# PrzyciskDotykowy_A4_Landscape.net
KiCad netlist of a schematic drawn in Altium Designer
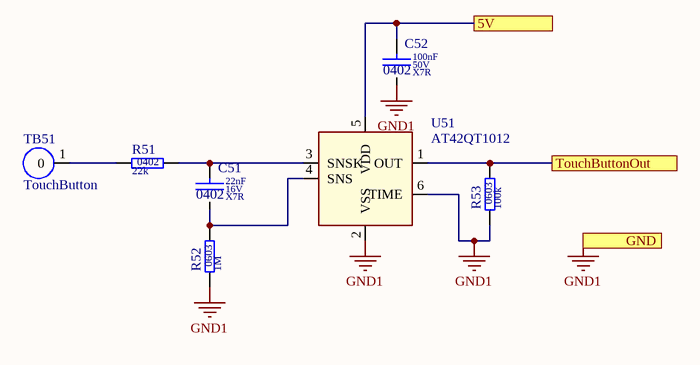
[diagram p0: PrzyciskDotykowy_A4_Landscape_.SchDoc]

(export (version "E")
  (design (tool "Eeschema 10.0.6"))
  (components
    (comp (ref "C51")
      (value "22nF")
      (footprint "C_0402_1005")
      (description "Capacitor")
      (fields
        (field (name "DIELECTRIC") "X7R")
        (field (name "VOLTAGE") "16V")
        (field (name "SCH_FOOTPRINT") "0402")
        (field (name "PART NUMBER") "C_22nF_16V_X7R_0402_10")
        (field (name "MANUFACTURER") "AVX")
      )
      (libsource (lib "Library") (part "C"))
    )
    (comp (ref "C52")
      (value "100nF")
      (footprint "C_0402_1005")
      (description "Capacitor")
      (fields
        (field (name "DIELECTRIC") "X7R")
        (field (name "VOLTAGE") "50V")
        (field (name "SCH_FOOTPRINT") "0402")
        (field (name "PART NUMBER") "C_100nF_50V_X7R_0402_10")
        (field (name "MANUFACTURER") "Murata")
      )
      (libsource (lib "Library") (part "C"))
    )
    (comp (ref "R51")
      (value "22k")
      (footprint "R_0402_1005")
      (fields
        (field (name "SCH_FOOTPRINT") "0402")
        (field (name "PART NUMBER") "R_22k_0402")
        (field (name "VOLTAGE") "50V")
        (field (name "POWER") "63mW")
      )
      (libsource (lib "Library") (part "R"))
    )
    (comp (ref "R52")
      (value "1M")
      (footprint "R_0603_1608")
      (fields
        (field (name "SCH_FOOTPRINT") "0603")
        (field (name "PART NUMBER") "R_1M_0603_1")
        (field (name "VOLTAGE") "50V")
        (field (name "POWER") "100mW")
      )
      (libsource (lib "Library") (part "R"))
    )
    (comp (ref "R53")
      (value "100k")
      (footprint "R_0603_1608")
      (fields
        (field (name "SCH_FOOTPRINT") "0603")
        (field (name "PART NUMBER") "R_100k_0603_1")
        (field (name "VOLTAGE") "50V")
        (field (name "POWER") "100mW")
      )
      (libsource (lib "Library") (part "R"))
    )
    (comp (ref "TB51")
      (value "TouchButton")
      (footprint "TouchButton")
      (libsource (lib "Integrated_Library1") (part "TouchButton"))
    )
    (comp (ref "U51")
      (value "AT42QT1012")
      (footprint "AT42QT1012")
      (libsource (lib "Integrated_Library1") (part "AT42QT1012"))
    )
  )
  (nets
    (net (code "1") (name "/5V") (class "Default")
      (node (ref "C52") (pin "1") (pinfunction "1_1") (pintype "passive"))
      (node (ref "U51") (pin "5") (pinfunction "VDD_5") (pintype "passive"))
    )
    (net (code "2") (name "/TouchButtonOut") (class "Default")
      (node (ref "R53") (pin "2") (pinfunction "2_2") (pintype "passive"))
      (node (ref "U51") (pin "1") (pinfunction "OUT_1") (pintype "passive"))
    )
    (net (code "3") (name "GND1") (class "Default")
      (node (ref "C52") (pin "2") (pinfunction "2_2") (pintype "passive"))
      (node (ref "R52") (pin "1") (pinfunction "1_1") (pintype "passive"))
      (node (ref "R53") (pin "1") (pinfunction "1_1") (pintype "passive"))
      (node (ref "U51") (pin "2") (pinfunction "VSS_2") (pintype "passive"))
      (node (ref "U51") (pin "6") (pinfunction "TIME_6") (pintype "passive"))
    )
    (net (code "4") (name "Net-(TB51-0)") (class "Default")
      (node (ref "R51") (pin "1") (pinfunction "1_1") (pintype "passive"))
      (node (ref "TB51") (pin "1") (pinfunction "0_1") (pintype "passive"))
    )
    (net (code "5") (name "Net-(U51-SNS)") (class "Default")
      (node (ref "C51") (pin "2") (pinfunction "2_2") (pintype "passive"))
      (node (ref "R52") (pin "2") (pinfunction "2_2") (pintype "passive"))
      (node (ref "U51") (pin "4") (pinfunction "SNS_4") (pintype "passive"))
    )
    (net (code "6") (name "Net-(U51-SNSK)") (class "Default")
      (node (ref "C51") (pin "1") (pinfunction "1_1") (pintype "passive"))
      (node (ref "R51") (pin "2") (pinfunction "2_2") (pintype "passive"))
      (node (ref "U51") (pin "3") (pinfunction "SNSK_3") (pintype "passive"))
    )
  )
)
